# AMC_SFP.net
KiCad netlist of a schematic drawn in Altium Designer
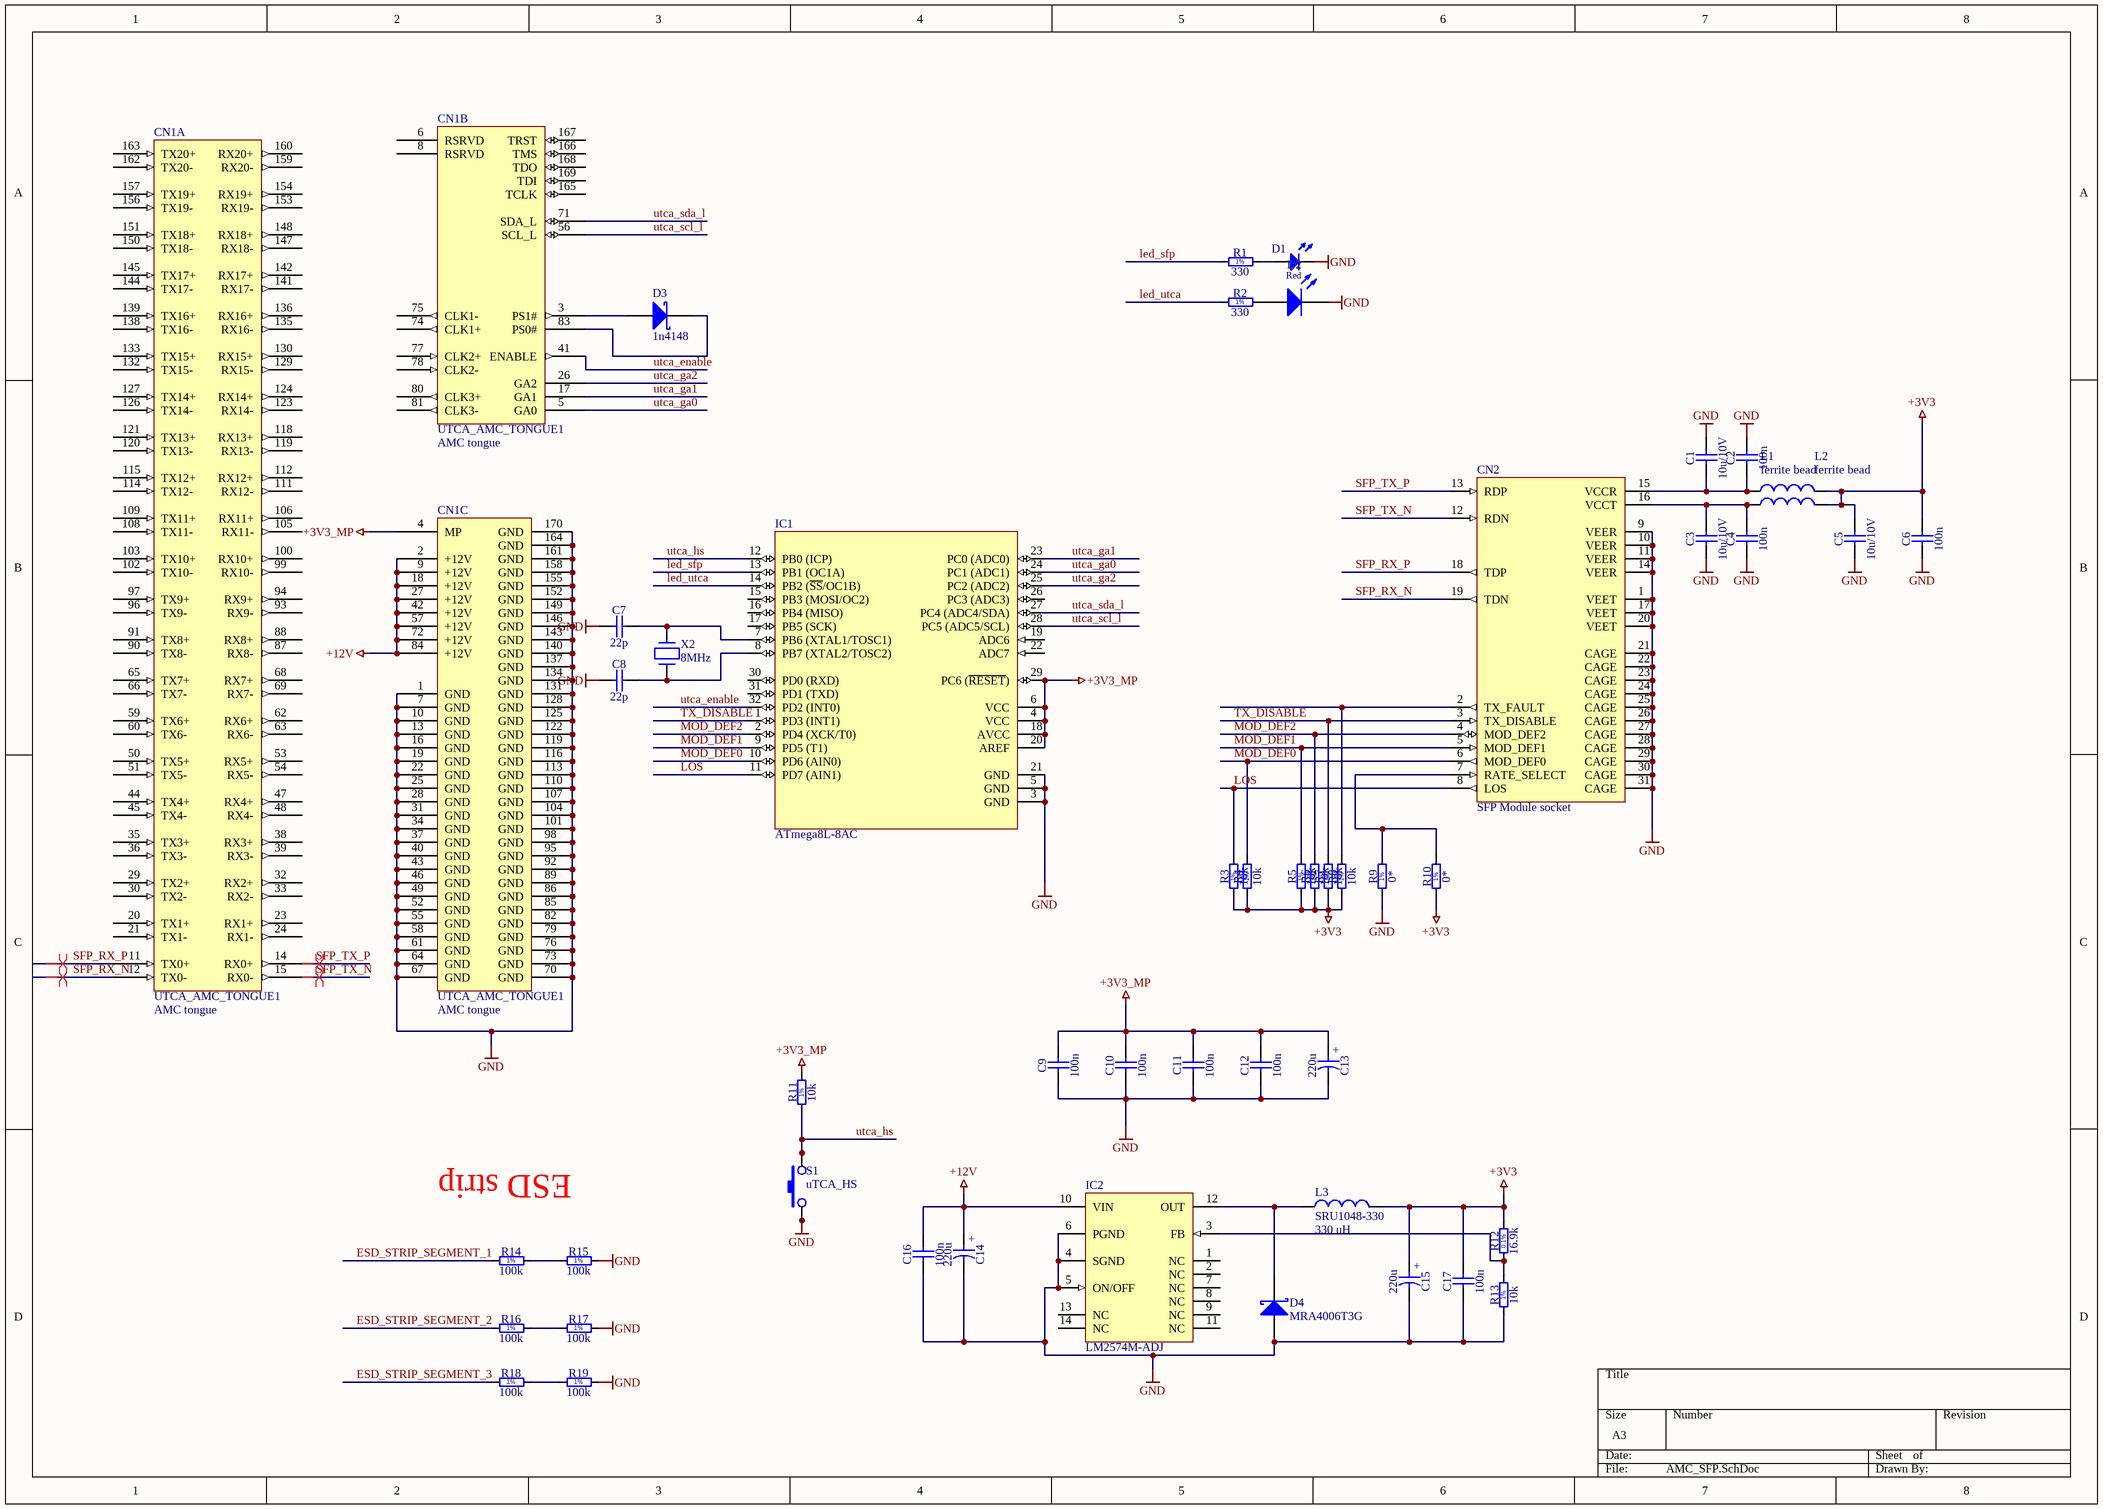
[diagram p0: AMC_SFP.SchDoc]

(export (version "E")
  (design (tool "Eeschema 10.0.6"))
  (components
    (comp (ref "C1")
      (value "10u/10V")
      (footprint "CAPC3216X140N")
      (description "Non-polarised capacitor")
      (fields
        (field (name "PART NUMBER") "CC1206_10UF_10V_10%_X7R")
        (field (name "VOLTAGE") "10V")
        (field (name "AUTHOR") "CERN DEM JLC")
      )
      (libsource (lib "Capacitors") (part "Capacitor - non polarized"))
    )
    (comp (ref "C2")
      (value "100n")
      (footprint "CAPC1608X87N")
      (description "Non-polarised capacitor")
      (fields
        (field (name "PART NUMBER") "CC0603_100NF_50V_10%_X7R")
        (field (name "VOLTAGE") "50V")
        (field (name "AUTHOR") "CERN DEM JLC")
      )
      (libsource (lib "Capacitors") (part "Capacitor - non polarized"))
    )
    (comp (ref "C3")
      (value "10u/10V")
      (footprint "CAPC3216X140N")
      (description "Non-polarised capacitor")
      (fields
        (field (name "PART NUMBER") "CC1206_10UF_10V_10%_X7R")
        (field (name "VOLTAGE") "10V")
        (field (name "AUTHOR") "CERN DEM JLC")
      )
      (libsource (lib "Capacitors") (part "Capacitor - non polarized"))
    )
    (comp (ref "C4")
      (value "100n")
      (footprint "CAPC1608X87N")
      (description "Non-polarised capacitor")
      (fields
        (field (name "PART NUMBER") "CC0603_100NF_50V_10%_X7R")
        (field (name "VOLTAGE") "50V")
        (field (name "AUTHOR") "CERN DEM JLC")
      )
      (libsource (lib "Capacitors") (part "Capacitor - non polarized"))
    )
    (comp (ref "C5")
      (value "10u/10V")
      (footprint "CAPC3216X140N")
      (description "Non-polarised capacitor")
      (fields
        (field (name "PART NUMBER") "CC1206_10UF_10V_10%_X7R")
        (field (name "VOLTAGE") "10V")
        (field (name "AUTHOR") "CERN DEM JLC")
      )
      (libsource (lib "Capacitors") (part "Capacitor - non polarized"))
    )
    (comp (ref "C6")
      (value "100n")
      (footprint "CAPC1608X87N")
      (description "Non-polarised capacitor")
      (fields
        (field (name "PART NUMBER") "CC0603_100NF_50V_10%_X7R")
        (field (name "VOLTAGE") "50V")
        (field (name "AUTHOR") "CERN DEM JLC")
      )
      (libsource (lib "Capacitors") (part "Capacitor - non polarized"))
    )
    (comp (ref "C7")
      (value "22p")
      (footprint "CAPC2012X135N")
      (description "Non-polarised capacitor")
      (fields
        (field (name "PART NUMBER") "CC0805_22PF_50V_5%_NP0")
        (field (name "VOLTAGE") "50V")
        (field (name "AUTHOR") "CERN DEM JLC")
      )
      (libsource (lib "Capacitors") (part "Capacitor - non polarized"))
    )
    (comp (ref "C8")
      (value "22p")
      (footprint "CAPC2012X135N")
      (description "Non-polarised capacitor")
      (fields
        (field (name "PART NUMBER") "CC0805_22PF_50V_5%_NP0")
        (field (name "VOLTAGE") "50V")
        (field (name "AUTHOR") "CERN DEM JLC")
      )
      (libsource (lib "Capacitors") (part "Capacitor - non polarized"))
    )
    (comp (ref "C9")
      (value "100n")
      (footprint "CAPC2012X135N")
      (description "Non-polarised capacitor")
      (fields
        (field (name "PART NUMBER") "CC0805_100NF_50V_10%_X7R")
        (field (name "VOLTAGE") "50V")
        (field (name "AUTHOR") "CERN DEM JLC")
      )
      (libsource (lib "Capacitors") (part "Capacitor - non polarized"))
    )
    (comp (ref "C10")
      (value "100n")
      (footprint "CAPC2012X135N")
      (description "Non-polarised capacitor")
      (fields
        (field (name "PART NUMBER") "CC0805_100NF_50V_10%_X7R")
        (field (name "VOLTAGE") "50V")
        (field (name "AUTHOR") "CERN DEM JLC")
      )
      (libsource (lib "Capacitors") (part "Capacitor - non polarized"))
    )
    (comp (ref "C11")
      (value "100n")
      (footprint "CAPC2012X135N")
      (description "Non-polarised capacitor")
      (fields
        (field (name "PART NUMBER") "CC0805_100NF_50V_10%_X7R")
        (field (name "VOLTAGE") "50V")
        (field (name "AUTHOR") "CERN DEM JLC")
      )
      (libsource (lib "Capacitors") (part "Capacitor - non polarized"))
    )
    (comp (ref "C12")
      (value "100n")
      (footprint "CAPC2012X135N")
      (description "Non-polarised capacitor")
      (fields
        (field (name "PART NUMBER") "CC0805_100NF_50V_10%_X7R")
        (field (name "VOLTAGE") "50V")
        (field (name "AUTHOR") "CERN DEM JLC")
      )
      (libsource (lib "Capacitors") (part "Capacitor - non polarized"))
    )
    (comp (ref "C13")
      (value "220u")
      (footprint "CAPPR350-850X600")
      (description "Polarised capacitor")
      (fields
        (field (name "PART NUMBER") "CAER_100UF_10V_20%_350-850X600_LESR0R032")
        (field (name "VOLTAGE") "10V")
        (field (name "AUTHOR") "CERN DEM JLC")
      )
      (libsource (lib "Capacitors") (part "Capacitor - polarized"))
    )
    (comp (ref "C14")
      (value "220u")
      (footprint "CAPPR350-850X600")
      (description "Polarised capacitor")
      (fields
        (field (name "PART NUMBER") "CAER_100UF_10V_20%_350-850X600_LESR0R032")
        (field (name "VOLTAGE") "10V")
        (field (name "AUTHOR") "CERN DEM JLC")
      )
      (libsource (lib "Capacitors") (part "Capacitor - polarized"))
    )
    (comp (ref "C15")
      (value "220u")
      (footprint "CAPPR350-850X600")
      (description "Polarised capacitor")
      (fields
        (field (name "PART NUMBER") "CAER_100UF_10V_20%_350-850X600_LESR0R032")
        (field (name "VOLTAGE") "10V")
        (field (name "AUTHOR") "CERN DEM JLC")
      )
      (libsource (lib "Capacitors") (part "Capacitor - polarized"))
    )
    (comp (ref "C16")
      (value "100n")
      (footprint "CAPC1608X87N")
      (description "Non-polarised capacitor")
      (fields
        (field (name "PART NUMBER") "CC0603_100NF_50V_10%_X7R")
        (field (name "VOLTAGE") "50V")
        (field (name "AUTHOR") "CERN DEM JLC")
      )
      (libsource (lib "Capacitors") (part "Capacitor - non polarized"))
    )
    (comp (ref "C17")
      (value "100n")
      (footprint "CAPC1608X87N")
      (description "Non-polarised capacitor")
      (fields
        (field (name "PART NUMBER") "CC0603_100NF_50V_10%_X7R")
        (field (name "VOLTAGE") "50V")
        (field (name "AUTHOR") "CERN DEM JLC")
      )
      (libsource (lib "Capacitors") (part "Capacitor - non polarized"))
    )
    (comp (ref "CN1")
      (value "UTCA_AMC_TONGUE1")
      (footprint "UTCA_AMC_TONGUE")
      (description "AMC1.0 connector")
      (fields (field (name "ALTIUM_VALUE") "AMC tongue"))
      (libsource (lib "wr_switch") (part "UTCA_AMC_TONGUE1"))
    )
    (comp (ref "CN2")
      (value "SFP Module socket")
      (footprint "SFP_SINGLE_PORT")
      (description "Socket for SFP module")
      (libsource (lib "wr_switch") (part "SFP_SOCKET_SINGLE"))
    )
    (comp (ref "D1")
      (value "Green")
      (footprint "LED_3MM_RED_1C-2A")
      (description "LED Red 1C 2A")
      (fields
        (field (name "PART NUMBER") "LED_AVAGO_HLMP-1700")
        (field (name "MANUFACTURER") "AVAGO TECHNOLOGIES")
        (field (name "AUTHOR") "CERN DEM JLC")
      )
      (libsource (lib "ICs And Semiconductors") (part "LED Red 1C 2A"))
    )
    (comp (ref "D2")
      (value "LED")
      (footprint "CD1608-0603")
      (description "Chip LED (any color)")
      (fields (field (name "PUBLISHER") "Altium Limited"))
      (libsource (lib "wr_switch") (part "LED0"))
    )
    (comp (ref "D3")
      (value "1n4148")
      (footprint "CD2012-0805")
      (description "Schottky Diode")
      (fields (field (name "PUBLISHER") "Altium Limited"))
      (libsource (lib "wr_switch") (part "D Schottky"))
    )
    (comp (ref "D4")
      (value "MRA4006T3G")
      (footprint "SMB")
      (description "Schottky Diode")
      (fields (field (name "PUBLISHER") "Altium Limited"))
      (libsource (lib "wr_switch") (part "D Schottky"))
    )
    (comp (ref "IC1")
      (value "ATmega8L-8AC")
      (footprint "32A_N")
      (description "8-Bit AVR Microcontroller with 8K Bytes of In-System Programmable Flash Memory")
      (fields (field (name "PUBLISHER") "Altium Limited"))
      (libsource (lib "Atmel Microcontroller 8-Bit AVR") (part "ATmega8L-8AC"))
    )
    (comp (ref "IC2")
      (value "LM2574M-ADJ")
      (footprint "M14B_N")
      (description "SIMPLE SWITCHER 0.5A Step-Down Voltage Regulator")
      (fields
        (field (name "MANUFACTURER") "National Semiconductor")
        (field (name "DIGIKEYPARTNUMBER") "LM2574M-ADJ-ND")
        (field (name "PUBLISHER") "Altium Limited")
      )
      (libsource (lib "NSC Switcher") (part "LM2574M-ADJ"))
    )
    (comp (ref "L1")
      (value "ferrite bead")
      (footprint "INDC2012-0805")
      (description "Ferrite bead")
      (fields (field (name "Comment") "Inductor") (field (name "PUBLISHER") "Altium Limited"))
      (libsource (lib "Miscellaneous Devices") (part "Inductor"))
    )
    (comp (ref "L2")
      (value "ferrite bead")
      (footprint "INDC2012-0805")
      (description "Ferrite bead")
      (fields (field (name "Comment") "Inductor") (field (name "PUBLISHER") "Altium Limited"))
      (libsource (lib "Miscellaneous Devices") (part "Inductor"))
    )
    (comp (ref "L3")
      (value "SRU1048-330")
      (footprint "L_BOURNS_SRU1048")
      (description "Inductor")
      (fields (field (name "ALTIUM_VALUE") "330 uH") (field (name "PUBLISHER") "Altium Limited"))
      (libsource (lib "wr_switch") (part "Inductor"))
    )
    (comp (ref "R1")
      (value "330")
      (footprint "RESC2012X60N")
      (description "Resistor - 1%")
      (fields
        (field (name "PART NUMBER") "R0805_330R_1%_0.125W_100PPM")
        (field (name "POWER") "0.125W")
        (field (name "AUTHOR") "CERN DEM JLC")
      )
      (libsource (lib "Resistors") (part "Resistor - 1%"))
    )
    (comp (ref "R2")
      (value "330")
      (footprint "RESC2012X60N")
      (description "Resistor - 1%")
      (fields
        (field (name "PART NUMBER") "R0805_330R_1%_0.125W_100PPM")
        (field (name "POWER") "0.125W")
        (field (name "AUTHOR") "CERN DEM JLC")
      )
      (libsource (lib "Resistors") (part "Resistor - 1%"))
    )
    (comp (ref "R3")
      (value "10k")
      (footprint "RESC1608X55N")
      (description "Resistor - 1%")
      (fields
        (field (name "PART NUMBER") "R0603_10K_1%_0.1W_100PPM")
        (field (name "POWER") "0.1W")
        (field (name "AUTHOR") "CERN DEM JLC")
      )
      (libsource (lib "Resistors") (part "Resistor - 1%"))
    )
    (comp (ref "R4")
      (value "10k")
      (footprint "RESC1608X55N")
      (description "Resistor - 1%")
      (fields
        (field (name "PART NUMBER") "R0603_10K_1%_0.1W_100PPM")
        (field (name "POWER") "0.1W")
        (field (name "AUTHOR") "CERN DEM JLC")
      )
      (libsource (lib "Resistors") (part "Resistor - 1%"))
    )
    (comp (ref "R5")
      (value "10k")
      (footprint "RESC1608X55N")
      (description "Resistor - 1%")
      (fields
        (field (name "PART NUMBER") "R0603_10K_1%_0.1W_100PPM")
        (field (name "POWER") "0.1W")
        (field (name "AUTHOR") "CERN DEM JLC")
      )
      (libsource (lib "Resistors") (part "Resistor - 1%"))
    )
    (comp (ref "R6")
      (value "10k")
      (footprint "RESC1608X55N")
      (description "Resistor - 1%")
      (fields
        (field (name "PART NUMBER") "R0603_10K_1%_0.1W_100PPM")
        (field (name "POWER") "0.1W")
        (field (name "AUTHOR") "CERN DEM JLC")
      )
      (libsource (lib "Resistors") (part "Resistor - 1%"))
    )
    (comp (ref "R7")
      (value "10k")
      (footprint "RESC1608X55N")
      (description "Resistor - 1%")
      (fields
        (field (name "PART NUMBER") "R0603_10K_1%_0.1W_100PPM")
        (field (name "POWER") "0.1W")
        (field (name "AUTHOR") "CERN DEM JLC")
      )
      (libsource (lib "Resistors") (part "Resistor - 1%"))
    )
    (comp (ref "R8")
      (value "10k")
      (footprint "RESC1608X55N")
      (description "Resistor - 1%")
      (fields
        (field (name "PART NUMBER") "R0603_10K_1%_0.1W_100PPM")
        (field (name "POWER") "0.1W")
        (field (name "AUTHOR") "CERN DEM JLC")
      )
      (libsource (lib "Resistors") (part "Resistor - 1%"))
    )
    (comp (ref "R9")
      (value "0*")
      (footprint "RESC1608X55N")
      (description "Resistor - 1%")
      (fields
        (field (name "PART NUMBER") "R0603_0R_JUMPER")
        (field (name "MANUFACTURER") "GENERIC")
        (field (name "AUTHOR") "CERN DEM JLC")
      )
      (libsource (lib "Resistors") (part "Resistor - 1%"))
    )
    (comp (ref "R10")
      (value "0*")
      (footprint "RESC1608X55N")
      (description "Resistor - 1%")
      (fields
        (field (name "PART NUMBER") "R0603_0R_JUMPER")
        (field (name "MANUFACTURER") "GENERIC")
        (field (name "AUTHOR") "CERN DEM JLC")
      )
      (libsource (lib "Resistors") (part "Resistor - 1%"))
    )
    (comp (ref "R11")
      (value "10k")
      (footprint "RESC1608X55N")
      (description "Resistor - 1%")
      (fields
        (field (name "PART NUMBER") "R0603_10K_1%_0.1W_100PPM")
        (field (name "POWER") "0.1W")
        (field (name "AUTHOR") "CERN DEM JLC")
      )
      (libsource (lib "Resistors") (part "Resistor - 1%"))
    )
    (comp (ref "R12")
      (value "16.9k")
      (footprint "RESC2012X60N")
      (description "Resistor - 0.1%")
      (fields
        (field (name "PART NUMBER") "R0805_16K9_0.1%_0.1W_10PPM")
        (field (name "POWER") "0.1W")
        (field (name "AUTHOR") "CERN DEM JLC")
      )
      (libsource (lib "Resistors") (part "Resistor - 0.1%"))
    )
    (comp (ref "R13")
      (value "10k")
      (footprint "RESC2012X60N")
      (description "Resistor - 1%")
      (fields
        (field (name "PART NUMBER") "R0805_10K_1%_0.125W_100PPM")
        (field (name "POWER") "0.125W")
        (field (name "AUTHOR") "CERN DEM JLC")
      )
      (libsource (lib "Resistors") (part "Resistor - 1%"))
    )
    (comp (ref "R14")
      (value "100k")
      (footprint "RESC3216X65N")
      (description "Resistor - 1%")
      (fields
        (field (name "PART NUMBER") "R1206_100K_1%_0.25W_100PPM")
        (field (name "POWER") "0.25W")
        (field (name "AUTHOR") "CERN DEM JLC")
      )
      (libsource (lib "Resistors") (part "Resistor - 1%"))
    )
    (comp (ref "R15")
      (value "100k")
      (footprint "RESC3216X65N")
      (description "Resistor - 1%")
      (fields
        (field (name "PART NUMBER") "R1206_100K_1%_0.25W_100PPM")
        (field (name "POWER") "0.25W")
        (field (name "AUTHOR") "CERN DEM JLC")
      )
      (libsource (lib "Resistors") (part "Resistor - 1%"))
    )
    (comp (ref "R16")
      (value "100k")
      (footprint "RESC3216X65N")
      (description "Resistor - 1%")
      (fields
        (field (name "PART NUMBER") "R1206_100K_1%_0.25W_100PPM")
        (field (name "POWER") "0.25W")
        (field (name "AUTHOR") "CERN DEM JLC")
      )
      (libsource (lib "Resistors") (part "Resistor - 1%"))
    )
    (comp (ref "R17")
      (value "100k")
      (footprint "RESC3216X65N")
      (description "Resistor - 1%")
      (fields
        (field (name "PART NUMBER") "R1206_100K_1%_0.25W_100PPM")
        (field (name "POWER") "0.25W")
        (field (name "AUTHOR") "CERN DEM JLC")
      )
      (libsource (lib "Resistors") (part "Resistor - 1%"))
    )
    (comp (ref "R18")
      (value "100k")
      (footprint "RESC3216X65N")
      (description "Resistor - 1%")
      (fields
        (field (name "PART NUMBER") "R1206_100K_1%_0.25W_100PPM")
        (field (name "POWER") "0.25W")
        (field (name "AUTHOR") "CERN DEM JLC")
      )
      (libsource (lib "Resistors") (part "Resistor - 1%"))
    )
    (comp (ref "R19")
      (value "100k")
      (footprint "RESC3216X65N")
      (description "Resistor - 1%")
      (fields
        (field (name "PART NUMBER") "R1206_100K_1%_0.25W_100PPM")
        (field (name "POWER") "0.25W")
        (field (name "AUTHOR") "CERN DEM JLC")
      )
      (libsource (lib "Resistors") (part "Resistor - 1%"))
    )
    (comp (ref "S1")
      (value "uTCA_HS")
      (footprint "uTCA_HOTSWAP_SWITCH")
      (description "Push button")
      (libsource (lib "wr_switch") (part "uTCA_HOTSWAP_SWITCH"))
    )
    (comp (ref "X2")
      (value "8MHz")
      (footprint "HC-49US")
      (description "Crystal oscillator")
      (libsource (lib "LIBRARY_SCH") (part "X_CRYSTAL"))
    )
  )
  (nets
    (net (code "1") (name "+3V3") (class "Default")
      (node (ref "C15") (pin "1") (pinfunction "1_1") (pintype "passive"))
      (node (ref "C17") (pin "2") (pinfunction "2_2") (pintype "passive"))
      (node (ref "C5") (pin "2") (pinfunction "2_2") (pintype "passive"))
      (node (ref "C6") (pin "2") (pinfunction "2_2") (pintype "passive"))
      (node (ref "L1") (pin "2") (pinfunction "2_2") (pintype "passive"))
      (node (ref "L2") (pin "2") (pinfunction "2_2") (pintype "passive"))
      (node (ref "L3") (pin "2") (pinfunction "2_2") (pintype "passive"))
      (node (ref "R10") (pin "1") (pinfunction "1_1") (pintype "passive"))
      (node (ref "R12") (pin "2") (pinfunction "2_2") (pintype "passive"))
      (node (ref "R3") (pin "1") (pinfunction "1_1") (pintype "passive"))
      (node (ref "R4") (pin "1") (pinfunction "1_1") (pintype "passive"))
      (node (ref "R5") (pin "1") (pinfunction "1_1") (pintype "passive"))
      (node (ref "R6") (pin "1") (pinfunction "1_1") (pintype "passive"))
      (node (ref "R7") (pin "1") (pinfunction "1_1") (pintype "passive"))
      (node (ref "R8") (pin "1") (pinfunction "1_1") (pintype "passive"))
    )
    (net (code "2") (name "+3V3_MP") (class "Default")
      (node (ref "C10") (pin "2") (pinfunction "2_2") (pintype "passive"))
      (node (ref "C11") (pin "2") (pinfunction "2_2") (pintype "passive"))
      (node (ref "C12") (pin "2") (pinfunction "2_2") (pintype "passive"))
      (node (ref "C13") (pin "1") (pinfunction "1_1") (pintype "passive"))
      (node (ref "C9") (pin "2") (pinfunction "2_2") (pintype "passive"))
      (node (ref "CN1") (pin "4") (pinfunction "MP_4") (pintype "power_in"))
      (node (ref "IC1") (pin "18") (pinfunction "AVCC_18") (pintype "power_in"))
      (node (ref "IC1") (pin "20") (pinfunction "AREF_20") (pintype "passive"))
      (node (ref "IC1") (pin "29") (pinfunction "PC6_(~{RESET})_29") (pintype "bidirectional"))
      (node (ref "IC1") (pin "4") (pinfunction "VCC_4") (pintype "power_in"))
      (node (ref "IC1") (pin "6") (pinfunction "VCC_6") (pintype "power_in"))
      (node (ref "R11") (pin "2") (pinfunction "2_2") (pintype "passive"))
    )
    (net (code "3") (name "+12V") (class "Default")
      (node (ref "C14") (pin "1") (pinfunction "1_1") (pintype "passive"))
      (node (ref "C16") (pin "2") (pinfunction "2_2") (pintype "passive"))
      (node (ref "CN1") (pin "18") (pinfunction "+12V_18") (pintype "power_in"))
      (node (ref "CN1") (pin "2") (pinfunction "+12V_2") (pintype "power_in"))
      (node (ref "CN1") (pin "27") (pinfunction "+12V_27") (pintype "power_in"))
      (node (ref "CN1") (pin "42") (pinfunction "+12V_42") (pintype "power_in"))
      (node (ref "CN1") (pin "57") (pinfunction "+12V_57") (pintype "power_in"))
      (node (ref "CN1") (pin "72") (pinfunction "+12V_72") (pintype "power_in"))
      (node (ref "CN1") (pin "84") (pinfunction "+12V_84") (pintype "power_in"))
      (node (ref "CN1") (pin "9") (pinfunction "+12V_9") (pintype "power_in"))
      (node (ref "IC2") (pin "10") (pinfunction "VIN_10") (pintype "power_in"))
    )
    (net (code "4") (name "/ESD_STRIP_SEGMENT_1") (class "Default")
      (node (ref "R14") (pin "1") (pinfunction "1_1") (pintype "passive"))
    )
    (net (code "5") (name "/ESD_STRIP_SEGMENT_2") (class "Default")
      (node (ref "R16") (pin "1") (pinfunction "1_1") (pintype "passive"))
    )
    (net (code "6") (name "/ESD_STRIP_SEGMENT_3") (class "Default")
      (node (ref "R18") (pin "1") (pinfunction "1_1") (pintype "passive"))
    )
    (net (code "7") (name "/LOS") (class "Default")
      (node (ref "CN2") (pin "8") (pinfunction "LOS_8") (pintype "output"))
      (node (ref "IC1") (pin "11") (pinfunction "PD7_(AIN1)_11") (pintype "bidirectional"))
      (node (ref "R3") (pin "2") (pinfunction "2_2") (pintype "passive"))
    )
    (net (code "8") (name "/MOD_DEF0") (class "Default")
      (node (ref "CN2") (pin "6") (pinfunction "MOD_DEF0_6") (pintype "output"))
      (node (ref "IC1") (pin "10") (pinfunction "PD6_(AIN0)_10") (pintype "bidirectional"))
      (node (ref "R4") (pin "2") (pinfunction "2_2") (pintype "passive"))
    )
    (net (code "9") (name "/MOD_DEF1") (class "Default")
      (node (ref "CN2") (pin "5") (pinfunction "MOD_DEF1_5") (pintype "input"))
      (node (ref "IC1") (pin "9") (pinfunction "PD5_(T1)_9") (pintype "bidirectional"))
      (node (ref "R5") (pin "2") (pinfunction "2_2") (pintype "passive"))
    )
    (net (code "10") (name "/MOD_DEF2") (class "Default")
      (node (ref "CN2") (pin "4") (pinfunction "MOD_DEF2_4") (pintype "bidirectional"))
      (node (ref "IC1") (pin "2") (pinfunction "PD4_(XCK/T0)_2") (pintype "bidirectional"))
      (node (ref "R6") (pin "2") (pinfunction "2_2") (pintype "passive"))
    )
    (net (code "11") (name "/SFP_RX_N") (class "Default")
      (node (ref "CN1") (pin "12") (pinfunction "TX0-_12") (pintype "input"))
      (node (ref "CN2") (pin "19") (pinfunction "TDN_19") (pintype "output"))
    )
    (net (code "12") (name "/SFP_RX_P") (class "Default")
      (node (ref "CN1") (pin "11") (pinfunction "TX0+_11") (pintype "input"))
      (node (ref "CN2") (pin "18") (pinfunction "TDP_18") (pintype "output"))
    )
    (net (code "13") (name "/SFP_TX_N") (class "Default")
      (node (ref "CN1") (pin "15") (pinfunction "RX0-_15") (pintype "output"))
      (node (ref "CN2") (pin "12") (pinfunction "RDN_12") (pintype "input"))
    )
    (net (code "14") (name "/SFP_TX_P") (class "Default")
      (node (ref "CN1") (pin "14") (pinfunction "RX0+_14") (pintype "output"))
      (node (ref "CN2") (pin "13") (pinfunction "RDP_13") (pintype "input"))
    )
    (net (code "15") (name "/TX_DISABLE") (class "Default")
      (node (ref "CN2") (pin "3") (pinfunction "TX_DISABLE_3") (pintype "input"))
      (node (ref "IC1") (pin "1") (pinfunction "PD3_(INT1)_1") (pintype "bidirectional"))
      (node (ref "R7") (pin "2") (pinfunction "2_2") (pintype "passive"))
    )
    (net (code "16") (name "/led_sfp") (class "Default")
      (node (ref "IC1") (pin "13") (pinfunction "PB1_(OC1A)_13") (pintype "bidirectional"))
      (node (ref "R1") (pin "1") (pinfunction "1_1") (pintype "passive"))
    )
    (net (code "17") (name "/led_utca") (class "Default")
      (node (ref "IC1") (pin "14") (pinfunction "PB2_(~{SS}/OC1B)_14") (pintype "bidirectional"))
      (node (ref "R2") (pin "1") (pinfunction "1_1") (pintype "passive"))
    )
    (net (code "18") (name "/utca_enable") (class "Default")
      (node (ref "CN1") (pin "41") (pinfunction "ENABLE_41") (pintype "output"))
      (node (ref "IC1") (pin "32") (pinfunction "PD2_(INT0)_32") (pintype "bidirectional"))
    )
    (net (code "19") (name "/utca_ga0") (class "Default")
      (node (ref "CN1") (pin "5") (pinfunction "GA0_5") (pintype "passive"))
      (node (ref "IC1") (pin "24") (pinfunction "PC1_(ADC1)_24") (pintype "bidirectional"))
    )
    (net (code "20") (name "/utca_ga1") (class "Default")
      (node (ref "CN1") (pin "17") (pinfunction "GA1_17") (pintype "passive"))
      (node (ref "IC1") (pin "23") (pinfunction "PC0_(ADC0)_23") (pintype "bidirectional"))
    )
    (net (code "21") (name "/utca_ga2") (class "Default")
      (node (ref "CN1") (pin "26") (pinfunction "GA2_26") (pintype "passive"))
      (node (ref "IC1") (pin "25") (pinfunction "PC2_(ADC2)_25") (pintype "bidirectional"))
    )
    (net (code "22") (name "/utca_hs") (class "Default")
      (node (ref "IC1") (pin "12") (pinfunction "PB0_(ICP)_12") (pintype "bidirectional"))
      (node (ref "R11") (pin "1") (pinfunction "1_1") (pintype "passive"))
      (node (ref "S1") (pin "B") (pinfunction "B_B") (pintype "passive"))
      (node (ref "S1") (pin "D") (pinfunction "D_D") (pintype "passive"))
    )
    (net (code "23") (name "/utca_scl_l") (class "Default")
      (node (ref "CN1") (pin "56") (pinfunction "SCL_L_56") (pintype "bidirectional"))
      (node (ref "IC1") (pin "28") (pinfunction "PC5_(ADC5/SCL)_28") (pintype "bidirectional"))
    )
    (net (code "24") (name "/utca_sda_l") (class "Default")
      (node (ref "CN1") (pin "71") (pinfunction "SDA_L_71") (pintype "bidirectional"))
      (node (ref "IC1") (pin "27") (pinfunction "PC4_(ADC4/SDA)_27") (pintype "bidirectional"))
    )
    (net (code "25") (name "GND") (class "Default")
      (node (ref "C1") (pin "2") (pinfunction "2_2") (pintype "passive"))
      (node (ref "C10") (pin "1") (pinfunction "1_1") (pintype "passive"))
      (node (ref "C11") (pin "1") (pinfunction "1_1") (pintype "passive"))
      (node (ref "C12") (pin "1") (pinfunction "1_1") (pintype "passive"))
      (node (ref "C13") (pin "2") (pinfunction "2_2") (pintype "passive"))
      (node (ref "C14") (pin "2") (pinfunction "2_2") (pintype "passive"))
      (node (ref "C15") (pin "2") (pinfunction "2_2") (pintype "passive"))
      (node (ref "C16") (pin "1") (pinfunction "1_1") (pintype "passive"))
      (node (ref "C17") (pin "1") (pinfunction "1_1") (pintype "passive"))
      (node (ref "C2") (pin "2") (pinfunction "2_2") (pintype "passive"))
      (node (ref "C3") (pin "1") (pinfunction "1_1") (pintype "passive"))
      (node (ref "C4") (pin "1") (pinfunction "1_1") (pintype "passive"))
      (node (ref "C5") (pin "1") (pinfunction "1_1") (pintype "passive"))
      (node (ref "C6") (pin "1") (pinfunction "1_1") (pintype "passive"))
      (node (ref "C7") (pin "1") (pinfunction "1_1") (pintype "passive"))
      (node (ref "C8") (pin "1") (pinfunction "1_1") (pintype "passive"))
      (node (ref "C9") (pin "1") (pinfunction "1_1") (pintype "passive"))
      (node (ref "CN1") (pin "1") (pinfunction "GND_1") (pintype "power_in"))
      (node (ref "CN1") (pin "10") (pinfunction "GND_10") (pintype "power_in"))
      (node (ref "CN1") (pin "101") (pinfunction "GND_101") (pintype "power_in"))
      (node (ref "CN1") (pin "104") (pinfunction "GND_104") (pintype "power_in"))
      (node (ref "CN1") (pin "107") (pinfunction "GND_107") (pintype "power_in"))
      (node (ref "CN1") (pin "110") (pinfunction "GND_110") (pintype "power_in"))
      (node (ref "CN1") (pin "113") (pinfunction "GND_113") (pintype "power_in"))
      (node (ref "CN1") (pin "116") (pinfunction "GND_116") (pintype "power_in"))
      (node (ref "CN1") (pin "119") (pinfunction "GND_119") (pintype "power_in"))
      (node (ref "CN1") (pin "122") (pinfunction "GND_122") (pintype "power_in"))
      (node (ref "CN1") (pin "125") (pinfunction "GND_125") (pintype "power_in"))
      (node (ref "CN1") (pin "128") (pinfunction "GND_128") (pintype "power_in"))
      (node (ref "CN1") (pin "13") (pinfunction "GND_13") (pintype "power_in"))
      (node (ref "CN1") (pin "131") (pinfunction "GND_131") (pintype "power_in"))
      (node (ref "CN1") (pin "134") (pinfunction "GND_134") (pintype "power_in"))
      (node (ref "CN1") (pin "137") (pinfunction "GND_137") (pintype "power_in"))
      (node (ref "CN1") (pin "140") (pinfunction "GND_140") (pintype "power_in"))
      (node (ref "CN1") (pin "143") (pinfunction "GND_143") (pintype "power_in"))
      (node (ref "CN1") (pin "146") (pinfunction "GND_146") (pintype "power_in"))
      (node (ref "CN1") (pin "149") (pinfunction "GND_149") (pintype "power_in"))
      (node (ref "CN1") (pin "152") (pinfunction "GND_152") (pintype "power_in"))
      (node (ref "CN1") (pin "155") (pinfunction "GND_155") (pintype "power_in"))
      (node (ref "CN1") (pin "158") (pinfunction "GND_158") (pintype "power_in"))
      (node (ref "CN1") (pin "16") (pinfunction "GND_16") (pintype "power_in"))
      (node (ref "CN1") (pin "161") (pinfunction "GND_161") (pintype "power_in"))
      (node (ref "CN1") (pin "164") (pinfunction "GND_164") (pintype "power_in"))
      (node (ref "CN1") (pin "170") (pinfunction "GND_170") (pintype "power_in"))
      (node (ref "CN1") (pin "19") (pinfunction "GND_19") (pintype "power_in"))
      (node (ref "CN1") (pin "22") (pinfunction "GND_22") (pintype "power_in"))
      (node (ref "CN1") (pin "25") (pinfunction "GND_25") (pintype "power_in"))
      (node (ref "CN1") (pin "28") (pinfunction "GND_28") (pintype "power_in"))
      (node (ref "CN1") (pin "31") (pinfunction "GND_31") (pintype "power_in"))
      (node (ref "CN1") (pin "34") (pinfunction "GND_34") (pintype "power_in"))
      (node (ref "CN1") (pin "37") (pinfunction "GND_37") (pintype "power_in"))
      (node (ref "CN1") (pin "40") (pinfunction "GND_40") (pintype "power_in"))
      (node (ref "CN1") (pin "43") (pinfunction "GND_43") (pintype "power_in"))
      (node (ref "CN1") (pin "46") (pinfunction "GND_46") (pintype "power_in"))
      (node (ref "CN1") (pin "49") (pinfunction "GND_49") (pintype "power_in"))
      (node (ref "CN1") (pin "52") (pinfunction "GND_52") (pintype "power_in"))
      (node (ref "CN1") (pin "55") (pinfunction "GND_55") (pintype "power_in"))
      (node (ref "CN1") (pin "58") (pinfunction "GND_58") (pintype "power_in"))
      (node (ref "CN1") (pin "61") (pinfunction "GND_61") (pintype "power_in"))
      (node (ref "CN1") (pin "64") (pinfunction "GND_64") (pintype "power_in"))
      (node (ref "CN1") (pin "67") (pinfunction "GND_67") (pintype "power_in"))
      (node (ref "CN1") (pin "7") (pinfunction "GND_7") (pintype "power_in"))
      (node (ref "CN1") (pin "70") (pinfunction "GND_70") (pintype "power_in"))
      (node (ref "CN1") (pin "73") (pinfunction "GND_73") (pintype "power_in"))
      (node (ref "CN1") (pin "76") (pinfunction "GND_76") (pintype "power_in"))
      (node (ref "CN1") (pin "79") (pinfunction "GND_79") (pintype "power_in"))
      (node (ref "CN1") (pin "82") (pinfunction "GND_82") (pintype "power_in"))
      (node (ref "CN1") (pin "85") (pinfunction "GND_85") (pintype "power_in"))
      (node (ref "CN1") (pin "86") (pinfunction "GND_86") (pintype "power_in"))
      (node (ref "CN1") (pin "89") (pinfunction "GND_89") (pintype "power_in"))
      (node (ref "CN1") (pin "92") (pinfunction "GND_92") (pintype "power_in"))
      (node (ref "CN1") (pin "95") (pinfunction "GND_95") (pintype "power_in"))
      (node (ref "CN1") (pin "98") (pinfunction "GND_98") (pintype "power_in"))
      (node (ref "CN2") (pin "1") (pinfunction "VEET_1") (pintype "power_in"))
      (node (ref "CN2") (pin "10") (pinfunction "VEER_10") (pintype "power_in"))
      (node (ref "CN2") (pin "11") (pinfunction "VEER_11") (pintype "power_in"))
      (node (ref "CN2") (pin "14") (pinfunction "VEER_14") (pintype "power_in"))
      (node (ref "CN2") (pin "17") (pinfunction "VEET_17") (pintype "power_in"))
      (node (ref "CN2") (pin "20") (pinfunction "VEET_20") (pintype "power_in"))
      (node (ref "CN2") (pin "21") (pinfunction "CAGE_21") (pintype "power_in"))
      (node (ref "CN2") (pin "22") (pinfunction "CAGE_22") (pintype "power_in"))
      (node (ref "CN2") (pin "23") (pinfunction "CAGE_23") (pintype "power_in"))
      (node (ref "CN2") (pin "24") (pinfunction "CAGE_24") (pintype "power_in"))
      (node (ref "CN2") (pin "25") (pinfunction "CAGE_25") (pintype "power_in"))
      (node (ref "CN2") (pin "26") (pinfunction "CAGE_26") (pintype "power_in"))
      (node (ref "CN2") (pin "27") (pinfunction "CAGE_27") (pintype "power_in"))
      (node (ref "CN2") (pin "28") (pinfunction "CAGE_28") (pintype "power_in"))
      (node (ref "CN2") (pin "29") (pinfunction "CAGE_29") (pintype "power_in"))
      (node (ref "CN2") (pin "30") (pinfunction "CAGE_30") (pintype "power_in"))
      (node (ref "CN2") (pin "31") (pinfunction "CAGE_31") (pintype "power_in"))
      (node (ref "CN2") (pin "9") (pinfunction "VEER_9") (pintype "power_in"))
      (node (ref "D1") (pin "1") (pinfunction "C_1") (pintype "passive"))
      (node (ref "D2") (pin "2") (pinfunction "K_2") (pintype "passive"))
      (node (ref "D4") (pin "1") (pinfunction "A_1") (pintype "passive"))
      (node (ref "IC1") (pin "21") (pinfunction "GND_21") (pintype "power_in"))
      (node (ref "IC1") (pin "3") (pinfunction "GND_3") (pintype "power_in"))
      (node (ref "IC1") (pin "5") (pinfunction "GND_5") (pintype "power_in"))
      (node (ref "IC2") (pin "4") (pinfunction "SGND_4") (pintype "power_in"))
      (node (ref "IC2") (pin "5") (pinfunction "ON/OFF_5") (pintype "input"))
      (node (ref "IC2") (pin "6") (pinfunction "PGND_6") (pintype "power_in"))
      (node (ref "R13") (pin "1") (pinfunction "1_1") (pintype "passive"))
      (node (ref "R15") (pin "2") (pinfunction "2_2") (pintype "passive"))
      (node (ref "R17") (pin "2") (pinfunction "2_2") (pintype "passive"))
      (node (ref "R19") (pin "2") (pinfunction "2_2") (pintype "passive"))
      (node (ref "R9") (pin "1") (pinfunction "1_1") (pintype "passive"))
      (node (ref "S1") (pin "A") (pinfunction "A_A") (pintype "passive"))
      (node (ref "S1") (pin "C") (pinfunction "C_C") (pintype "passive"))
    )
    (net (code "26") (name "Net-(CN1B-PS0#)") (class "Default")
      (node (ref "CN1") (pin "83") (pinfunction "PS0#_83") (pintype "passive"))
      (node (ref "D3") (pin "2") (pinfunction "K_2") (pintype "passive"))
    )
    (net (code "27") (name "Net-(CN1B-PS1#)") (class "Default")
      (node (ref "CN1") (pin "3") (pinfunction "PS1#_3") (pintype "output"))
      (node (ref "D3") (pin "1") (pinfunction "A_1") (pintype "passive"))
    )
    (net (code "28") (name "Net-(CN2-RATE_SELECT)") (class "Default")
      (node (ref "CN2") (pin "7") (pinfunction "RATE_SELECT_7") (pintype "input"))
      (node (ref "R10") (pin "2") (pinfunction "2_2") (pintype "passive"))
      (node (ref "R9") (pin "2") (pinfunction "2_2") (pintype "passive"))
    )
    (net (code "29") (name "Net-(CN2-TX_FAULT)") (class "Default")
      (node (ref "CN2") (pin "2") (pinfunction "TX_FAULT_2") (pintype "output"))
      (node (ref "R8") (pin "2") (pinfunction "2_2") (pintype "passive"))
    )
    (net (code "30") (name "Net-(CN2-VCCR)") (class "Default")
      (node (ref "C1") (pin "1") (pinfunction "1_1") (pintype "passive"))
      (node (ref "C2") (pin "1") (pinfunction "1_1") (pintype "passive"))
      (node (ref "CN2") (pin "15") (pinfunction "VCCR_15") (pintype "power_in"))
      (node (ref "L2") (pin "1") (pinfunction "1_1") (pintype "passive"))
    )
    (net (code "31") (name "Net-(CN2-VCCT)") (class "Default")
      (node (ref "C3") (pin "2") (pinfunction "2_2") (pintype "passive"))
      (node (ref "C4") (pin "2") (pinfunction "2_2") (pintype "passive"))
      (node (ref "CN2") (pin "16") (pinfunction "VCCT_16") (pintype "power_in"))
      (node (ref "L1") (pin "1") (pinfunction "1_1") (pintype "passive"))
    )
    (net (code "32") (name "Net-(D1-A)") (class "Default")
      (node (ref "D1") (pin "2") (pinfunction "A_2") (pintype "passive"))
      (node (ref "R1") (pin "2") (pinfunction "2_2") (pintype "passive"))
    )
    (net (code "33") (name "Net-(D2-A)") (class "Default")
      (node (ref "D2") (pin "1") (pinfunction "A_1") (pintype "passive"))
      (node (ref "R2") (pin "2") (pinfunction "2_2") (pintype "passive"))
    )
    (net (code "34") (name "Net-(D4-K)") (class "Default")
      (node (ref "D4") (pin "2") (pinfunction "K_2") (pintype "passive"))
      (node (ref "IC2") (pin "12") (pinfunction "OUT_12") (pintype "power_in"))
      (node (ref "L3") (pin "1") (pinfunction "1_1") (pintype "passive"))
    )
    (net (code "35") (name "Net-(IC1-PB6_(XTAL1{slash}TOSC1))") (class "Default")
      (node (ref "C7") (pin "2") (pinfunction "2_2") (pintype "passive"))
      (node (ref "IC1") (pin "7") (pinfunction "PB6_(XTAL1/TOSC1)_7") (pintype "bidirectional"))
      (node (ref "X2") (pin "2") (pinfunction "2_2") (pintype "passive"))
    )
    (net (code "36") (name "Net-(IC1-PB7_(XTAL2{slash}TOSC2))") (class "Default")
      (node (ref "C8") (pin "2") (pinfunction "2_2") (pintype "passive"))
      (node (ref "IC1") (pin "8") (pinfunction "PB7_(XTAL2/TOSC2)_8") (pintype "bidirectional"))
      (node (ref "X2") (pin "1") (pinfunction "1_1") (pintype "passive"))
    )
    (net (code "37") (name "Net-(IC2-FB)") (class "Default")
      (node (ref "IC2") (pin "3") (pinfunction "FB_3") (pintype "input"))
      (node (ref "R12") (pin "1") (pinfunction "1_1") (pintype "passive"))
      (node (ref "R13") (pin "2") (pinfunction "2_2") (pintype "passive"))
    )
    (net (code "38") (name "Net-(R14-Pad2)") (class "Default")
      (node (ref "R14") (pin "2") (pinfunction "2_2") (pintype "passive"))
      (node (ref "R15") (pin "1") (pinfunction "1_1") (pintype "passive"))
    )
    (net (code "39") (name "Net-(R16-Pad2)") (class "Default")
      (node (ref "R16") (pin "2") (pinfunction "2_2") (pintype "passive"))
      (node (ref "R17") (pin "1") (pinfunction "1_1") (pintype "passive"))
    )
    (net (code "40") (name "Net-(R18-Pad2)") (class "Default")
      (node (ref "R18") (pin "2") (pinfunction "2_2") (pintype "passive"))
      (node (ref "R19") (pin "1") (pinfunction "1_1") (pintype "passive"))
    )
    (net (code "41") (name "unconnected-(CN1A-RX1+-Pad23)") (class "Default")
      (node (ref "CN1") (pin "23") (pinfunction "RX1+_23") (pintype "output"))
    )
    (net (code "42") (name "unconnected-(CN1A-RX1--Pad24)") (class "Default")
      (node (ref "CN1") (pin "24") (pinfunction "RX1-_24") (pintype "output"))
    )
    (net (code "43") (name "unconnected-(CN1A-RX2+-Pad32)") (class "Default")
      (node (ref "CN1") (pin "32") (pinfunction "RX2+_32") (pintype "output"))
    )
    (net (code "44") (name "unconnected-(CN1A-RX2--Pad33)") (class "Default")
      (node (ref "CN1") (pin "33") (pinfunction "RX2-_33") (pintype "output"))
    )
    (net (code "45") (name "unconnected-(CN1A-RX3+-Pad38)") (class "Default")
      (node (ref "CN1") (pin "38") (pinfunction "RX3+_38") (pintype "output"))
    )
    (net (code "46") (name "unconnected-(CN1A-RX3--Pad39)") (class "Default")
      (node (ref "CN1") (pin "39") (pinfunction "RX3-_39") (pintype "output"))
    )
    (net (code "47") (name "unconnected-(CN1A-RX4+-Pad47)") (class "Default")
      (node (ref "CN1") (pin "47") (pinfunction "RX4+_47") (pintype "output"))
    )
    (net (code "48") (name "unconnected-(CN1A-RX4--Pad48)") (class "Default")
      (node (ref "CN1") (pin "48") (pinfunction "RX4-_48") (pintype "output"))
    )
    (net (code "49") (name "unconnected-(CN1A-RX5+-Pad53)") (class "Default")
      (node (ref "CN1") (pin "53") (pinfunction "RX5+_53") (pintype "output"))
    )
    (net (code "50") (name "unconnected-(CN1A-RX5--Pad54)") (class "Default")
      (node (ref "CN1") (pin "54") (pinfunction "RX5-_54") (pintype "output"))
    )
    (net (code "51") (name "unconnected-(CN1A-RX6+-Pad62)") (class "Default")
      (node (ref "CN1") (pin "62") (pinfunction "RX6+_62") (pintype "output"))
    )
    (net (code "52") (name "unconnected-(CN1A-RX6--Pad63)") (class "Default")
      (node (ref "CN1") (pin "63") (pinfunction "RX6-_63") (pintype "output"))
    )
    (net (code "53") (name "unconnected-(CN1A-RX7+-Pad68)") (class "Default")
      (node (ref "CN1") (pin "68") (pinfunction "RX7+_68") (pintype "output"))
    )
    (net (code "54") (name "unconnected-(CN1A-RX7--Pad69)") (class "Default")
      (node (ref "CN1") (pin "69") (pinfunction "RX7-_69") (pintype "output"))
    )
    (net (code "55") (name "unconnected-(CN1A-RX8+-Pad88)") (class "Default")
      (node (ref "CN1") (pin "88") (pinfunction "RX8+_88") (pintype "output"))
    )
    (net (code "56") (name "unconnected-(CN1A-RX8--Pad87)") (class "Default")
      (node (ref "CN1") (pin "87") (pinfunction "RX8-_87") (pintype "output"))
    )
    (net (code "57") (name "unconnected-(CN1A-RX9+-Pad94)") (class "Default")
      (node (ref "CN1") (pin "94") (pinfunction "RX9+_94") (pintype "output"))
    )
    (net (code "58") (name "unconnected-(CN1A-RX9--Pad93)") (class "Default")
      (node (ref "CN1") (pin "93") (pinfunction "RX9-_93") (pintype "output"))
    )
    (net (code "59") (name "unconnected-(CN1A-RX10+-Pad100)") (class "Default")
      (node (ref "CN1") (pin "100") (pinfunction "RX10+_100") (pintype "output"))
    )
    (net (code "60") (name "unconnected-(CN1A-RX10--Pad99)") (class "Default")
      (node (ref "CN1") (pin "99") (pinfunction "RX10-_99") (pintype "output"))
    )
    (net (code "61") (name "unconnected-(CN1A-RX11+-Pad106)") (class "Default")
      (node (ref "CN1") (pin "106") (pinfunction "RX11+_106") (pintype "output"))
    )
    (net (code "62") (name "unconnected-(CN1A-RX11--Pad105)") (class "Default")
      (node (ref "CN1") (pin "105") (pinfunction "RX11-_105") (pintype "output"))
    )
    (net (code "63") (name "unconnected-(CN1A-RX12+-Pad112)") (class "Default")
      (node (ref "CN1") (pin "112") (pinfunction "RX12+_112") (pintype "output"))
    )
    (net (code "64") (name "unconnected-(CN1A-RX12--Pad111)") (class "Default")
      (node (ref "CN1") (pin "111") (pinfunction "RX12-_111") (pintype "output"))
    )
    (net (code "65") (name "unconnected-(CN1A-RX13+-Pad118)") (class "Default")
      (node (ref "CN1") (pin "118") (pinfunction "RX13+_118") (pintype "output"))
    )
    (net (code "66") (name "unconnected-(CN1A-RX13--Pad119)") (class "Default")
      (node (ref "CN1") (pin "119") (pinfunction "RX13-_119") (pintype "output"))
    )
    (net (code "67") (name "unconnected-(CN1A-RX14+-Pad124)") (class "Default")
      (node (ref "CN1") (pin "124") (pinfunction "RX14+_124") (pintype "output"))
    )
    (net (code "68") (name "unconnected-(CN1A-RX14--Pad123)") (class "Default")
      (node (ref "CN1") (pin "123") (pinfunction "RX14-_123") (pintype "output"))
    )
    (net (code "69") (name "unconnected-(CN1A-RX15+-Pad130)") (class "Default")
      (node (ref "CN1") (pin "130") (pinfunction "RX15+_130") (pintype "output"))
    )
    (net (code "70") (name "unconnected-(CN1A-RX15--Pad129)") (class "Default")
      (node (ref "CN1") (pin "129") (pinfunction "RX15-_129") (pintype "output"))
    )
    (net (code "71") (name "unconnected-(CN1A-RX16+-Pad136)") (class "Default")
      (node (ref "CN1") (pin "136") (pinfunction "RX16+_136") (pintype "output"))
    )
    (net (code "72") (name "unconnected-(CN1A-RX16--Pad135)") (class "Default")
      (node (ref "CN1") (pin "135") (pinfunction "RX16-_135") (pintype "output"))
    )
    (net (code "73") (name "unconnected-(CN1A-RX17+-Pad142)") (class "Default")
      (node (ref "CN1") (pin "142") (pinfunction "RX17+_142") (pintype "output"))
    )
    (net (code "74") (name "unconnected-(CN1A-RX17--Pad141)") (class "Default")
      (node (ref "CN1") (pin "141") (pinfunction "RX17-_141") (pintype "output"))
    )
    (net (code "75") (name "unconnected-(CN1A-RX18+-Pad148)") (class "Default")
      (node (ref "CN1") (pin "148") (pinfunction "RX18+_148") (pintype "output"))
    )
    (net (code "76") (name "unconnected-(CN1A-RX18--Pad147)") (class "Default")
      (node (ref "CN1") (pin "147") (pinfunction "RX18-_147") (pintype "output"))
    )
    (net (code "77") (name "unconnected-(CN1A-RX19+-Pad154)") (class "Default")
      (node (ref "CN1") (pin "154") (pinfunction "RX19+_154") (pintype "output"))
    )
    (net (code "78") (name "unconnected-(CN1A-RX19--Pad153)") (class "Default")
      (node (ref "CN1") (pin "153") (pinfunction "RX19-_153") (pintype "output"))
    )
    (net (code "79") (name "unconnected-(CN1A-RX20+-Pad160)") (class "Default")
      (node (ref "CN1") (pin "160") (pinfunction "RX20+_160") (pintype "output"))
    )
    (net (code "80") (name "unconnected-(CN1A-RX20--Pad159)") (class "Default")
      (node (ref "CN1") (pin "159") (pinfunction "RX20-_159") (pintype "output"))
    )
    (net (code "81") (name "unconnected-(CN1A-TX1+-Pad20)") (class "Default")
      (node (ref "CN1") (pin "20") (pinfunction "TX1+_20") (pintype "input"))
    )
    (net (code "82") (name "unconnected-(CN1A-TX1--Pad21)") (class "Default")
      (node (ref "CN1") (pin "21") (pinfunction "TX1-_21") (pintype "input"))
    )
    (net (code "83") (name "unconnected-(CN1A-TX2+-Pad29)") (class "Default")
      (node (ref "CN1") (pin "29") (pinfunction "TX2+_29") (pintype "input"))
    )
    (net (code "84") (name "unconnected-(CN1A-TX2--Pad30)") (class "Default")
      (node (ref "CN1") (pin "30") (pinfunction "TX2-_30") (pintype "input"))
    )
    (net (code "85") (name "unconnected-(CN1A-TX3+-Pad35)") (class "Default")
      (node (ref "CN1") (pin "35") (pinfunction "TX3+_35") (pintype "input"))
    )
    (net (code "86") (name "unconnected-(CN1A-TX3--Pad36)") (class "Default")
      (node (ref "CN1") (pin "36") (pinfunction "TX3-_36") (pintype "input"))
    )
    (net (code "87") (name "unconnected-(CN1A-TX4+-Pad44)") (class "Default")
      (node (ref "CN1") (pin "44") (pinfunction "TX4+_44") (pintype "input"))
    )
    (net (code "88") (name "unconnected-(CN1A-TX4--Pad45)") (class "Default")
      (node (ref "CN1") (pin "45") (pinfunction "TX4-_45") (pintype "input"))
    )
    (net (code "89") (name "unconnected-(CN1A-TX5+-Pad50)") (class "Default")
      (node (ref "CN1") (pin "50") (pinfunction "TX5+_50") (pintype "input"))
    )
    (net (code "90") (name "unconnected-(CN1A-TX5--Pad51)") (class "Default")
      (node (ref "CN1") (pin "51") (pinfunction "TX5-_51") (pintype "input"))
    )
    (net (code "91") (name "unconnected-(CN1A-TX6+-Pad59)") (class "Default")
      (node (ref "CN1") (pin "59") (pinfunction "TX6+_59") (pintype "input"))
    )
    (net (code "92") (name "unconnected-(CN1A-TX6--Pad60)") (class "Default")
      (node (ref "CN1") (pin "60") (pinfunction "TX6-_60") (pintype "input"))
    )
    (net (code "93") (name "unconnected-(CN1A-TX7+-Pad65)") (class "Default")
      (node (ref "CN1") (pin "65") (pinfunction "TX7+_65") (pintype "input"))
    )
    (net (code "94") (name "unconnected-(CN1A-TX7--Pad66)") (class "Default")
      (node (ref "CN1") (pin "66") (pinfunction "TX7-_66") (pintype "input"))
    )
    (net (code "95") (name "unconnected-(CN1A-TX8+-Pad91)") (class "Default")
      (node (ref "CN1") (pin "91") (pinfunction "TX8+_91") (pintype "input"))
    )
    (net (code "96") (name "unconnected-(CN1A-TX8--Pad90)") (class "Default")
      (node (ref "CN1") (pin "90") (pinfunction "TX8-_90") (pintype "input"))
    )
    (net (code "97") (name "unconnected-(CN1A-TX9+-Pad97)") (class "Default")
      (node (ref "CN1") (pin "97") (pinfunction "TX9+_97") (pintype "input"))
    )
    (net (code "98") (name "unconnected-(CN1A-TX9--Pad96)") (class "Default")
      (node (ref "CN1") (pin "96") (pinfunction "TX9-_96") (pintype "input"))
    )
    (net (code "99") (name "unconnected-(CN1A-TX10+-Pad103)") (class "Default")
      (node (ref "CN1") (pin "103") (pinfunction "TX10+_103") (pintype "input"))
    )
    (net (code "100") (name "unconnected-(CN1A-TX10--Pad102)") (class "Default")
      (node (ref "CN1") (pin "102") (pinfunction "TX10-_102") (pintype "input"))
    )
    (net (code "101") (name "unconnected-(CN1A-TX11+-Pad109)") (class "Default")
      (node (ref "CN1") (pin "109") (pinfunction "TX11+_109") (pintype "input"))
    )
    (net (code "102") (name "unconnected-(CN1A-TX11--Pad108)") (class "Default")
      (node (ref "CN1") (pin "108") (pinfunction "TX11-_108") (pintype "input"))
    )
    (net (code "103") (name "unconnected-(CN1A-TX12+-Pad115)") (class "Default")
      (node (ref "CN1") (pin "115") (pinfunction "TX12+_115") (pintype "input"))
    )
    (net (code "104") (name "unconnected-(CN1A-TX12--Pad114)") (class "Default")
      (node (ref "CN1") (pin "114") (pinfunction "TX12-_114") (pintype "input"))
    )
    (net (code "105") (name "unconnected-(CN1A-TX13+-Pad121)") (class "Default")
      (node (ref "CN1") (pin "121") (pinfunction "TX13+_121") (pintype "input"))
    )
    (net (code "106") (name "unconnected-(CN1A-TX13--Pad120)") (class "Default")
      (node (ref "CN1") (pin "120") (pinfunction "TX13-_120") (pintype "input"))
    )
    (net (code "107") (name "unconnected-(CN1A-TX14+-Pad127)") (class "Default")
      (node (ref "CN1") (pin "127") (pinfunction "TX14+_127") (pintype "input"))
    )
    (net (code "108") (name "unconnected-(CN1A-TX14--Pad126)") (class "Default")
      (node (ref "CN1") (pin "126") (pinfunction "TX14-_126") (pintype "input"))
    )
    (net (code "109") (name "unconnected-(CN1A-TX15+-Pad133)") (class "Default")
      (node (ref "CN1") (pin "133") (pinfunction "TX15+_133") (pintype "input"))
    )
    (net (code "110") (name "unconnected-(CN1A-TX15--Pad132)") (class "Default")
      (node (ref "CN1") (pin "132") (pinfunction "TX15-_132") (pintype "input"))
    )
    (net (code "111") (name "unconnected-(CN1A-TX16+-Pad139)") (class "Default")
      (node (ref "CN1") (pin "139") (pinfunction "TX16+_139") (pintype "input"))
    )
    (net (code "112") (name "unconnected-(CN1A-TX16--Pad138)") (class "Default")
      (node (ref "CN1") (pin "138") (pinfunction "TX16-_138") (pintype "input"))
    )
    (net (code "113") (name "unconnected-(CN1A-TX17+-Pad145)") (class "Default")
      (node (ref "CN1") (pin "145") (pinfunction "TX17+_145") (pintype "input"))
    )
    (net (code "114") (name "unconnected-(CN1A-TX17--Pad144)") (class "Default")
      (node (ref "CN1") (pin "144") (pinfunction "TX17-_144") (pintype "input"))
    )
    (net (code "115") (name "unconnected-(CN1A-TX18+-Pad151)") (class "Default")
      (node (ref "CN1") (pin "151") (pinfunction "TX18+_151") (pintype "input"))
    )
    (net (code "116") (name "unconnected-(CN1A-TX18--Pad150)") (class "Default")
      (node (ref "CN1") (pin "150") (pinfunction "TX18-_150") (pintype "input"))
    )
    (net (code "117") (name "unconnected-(CN1A-TX19+-Pad157)") (class "Default")
      (node (ref "CN1") (pin "157") (pinfunction "TX19+_157") (pintype "input"))
    )
    (net (code "118") (name "unconnected-(CN1A-TX19--Pad156)") (class "Default")
      (node (ref "CN1") (pin "156") (pinfunction "TX19-_156") (pintype "input"))
    )
    (net (code "119") (name "unconnected-(CN1A-TX20+-Pad163)") (class "Default")
      (node (ref "CN1") (pin "163") (pinfunction "TX20+_163") (pintype "input"))
    )
    (net (code "120") (name "unconnected-(CN1A-TX20--Pad162)") (class "Default")
      (node (ref "CN1") (pin "162") (pinfunction "TX20-_162") (pintype "input"))
    )
    (net (code "121") (name "unconnected-(CN1B-CLK1+-Pad74)") (class "Default")
      (node (ref "CN1") (pin "74") (pinfunction "CLK1+_74") (pintype "output"))
    )
    (net (code "122") (name "unconnected-(CN1B-CLK1--Pad75)") (class "Default")
      (node (ref "CN1") (pin "75") (pinfunction "CLK1-_75") (pintype "output"))
    )
    (net (code "123") (name "unconnected-(CN1B-CLK2+-Pad77)") (class "Default")
      (node (ref "CN1") (pin "77") (pinfunction "CLK2+_77") (pintype "input"))
    )
    (net (code "124") (name "unconnected-(CN1B-CLK2--Pad78)") (class "Default")
      (node (ref "CN1") (pin "78") (pinfunction "CLK2-_78") (pintype "input"))
    )
    (net (code "125") (name "unconnected-(CN1B-CLK3+-Pad80)") (class "Default")
      (node (ref "CN1") (pin "80") (pinfunction "CLK3+_80") (pintype "output"))
    )
    (net (code "126") (name "unconnected-(CN1B-CLK3--Pad81)") (class "Default")
      (node (ref "CN1") (pin "81") (pinfunction "CLK3-_81") (pintype "output"))
    )
    (net (code "127") (name "unconnected-(CN1B-RSRVD-Pad6)") (class "Default")
      (node (ref "CN1") (pin "6") (pinfunction "RSRVD_6") (pintype "passive"))
    )
    (net (code "128") (name "unconnected-(CN1B-RSRVD-Pad8)") (class "Default")
      (node (ref "CN1") (pin "8") (pinfunction "RSRVD_8") (pintype "passive"))
    )
    (net (code "129") (name "unconnected-(CN1B-TCLK-Pad165)") (class "Default")
      (node (ref "CN1") (pin "165") (pinfunction "TCLK_165") (pintype "bidirectional"))
    )
    (net (code "130") (name "unconnected-(CN1B-TDI-Pad169)") (class "Default")
      (node (ref "CN1") (pin "169") (pinfunction "TDI_169") (pintype "bidirectional"))
    )
    (net (code "131") (name "unconnected-(CN1B-TDO-Pad168)") (class "Default")
      (node (ref "CN1") (pin "168") (pinfunction "TDO_168") (pintype "bidirectional"))
    )
    (net (code "132") (name "unconnected-(CN1B-TMS-Pad166)") (class "Default")
      (node (ref "CN1") (pin "166") (pinfunction "TMS_166") (pintype "bidirectional"))
    )
    (net (code "133") (name "unconnected-(CN1B-TRST-Pad167)") (class "Default")
      (node (ref "CN1") (pin "167") (pinfunction "TRST_167") (pintype "bidirectional"))
    )
    (net (code "134") (name "unconnected-(IC1-ADC6-Pad19)") (class "Default")
      (node (ref "IC1") (pin "19") (pinfunction "ADC6_19") (pintype "input"))
    )
    (net (code "135") (name "unconnected-(IC1-ADC7-Pad22)") (class "Default")
      (node (ref "IC1") (pin "22") (pinfunction "ADC7_22") (pintype "input"))
    )
    (net (code "136") (name "unconnected-(IC1-PB3_(MOSI{slash}OC2)-Pad15)") (class "Default")
      (node (ref "IC1") (pin "15") (pinfunction "PB3_(MOSI/OC2)_15") (pintype "bidirectional"))
    )
    (net (code "137") (name "unconnected-(IC1-PB4_(MISO)-Pad16)") (class "Default")
      (node (ref "IC1") (pin "16") (pinfunction "PB4_(MISO)_16") (pintype "bidirectional"))
    )
    (net (code "138") (name "unconnected-(IC1-PB5_(SCK)-Pad17)") (class "Default")
      (node (ref "IC1") (pin "17") (pinfunction "PB5_(SCK)_17") (pintype "bidirectional"))
    )
    (net (code "139") (name "unconnected-(IC1-PC3_(ADC3)-Pad26)") (class "Default")
      (node (ref "IC1") (pin "26") (pinfunction "PC3_(ADC3)_26") (pintype "bidirectional"))
    )
    (net (code "140") (name "unconnected-(IC1-PD0_(RXD)-Pad30)") (class "Default")
      (node (ref "IC1") (pin "30") (pinfunction "PD0_(RXD)_30") (pintype "bidirectional"))
    )
    (net (code "141") (name "unconnected-(IC1-PD1_(TXD)-Pad31)") (class "Default")
      (node (ref "IC1") (pin "31") (pinfunction "PD1_(TXD)_31") (pintype "bidirectional"))
    )
    (net (code "142") (name "unconnected-(IC2-NC-Pad1)") (class "Default")
      (node (ref "IC2") (pin "1") (pinfunction "NC_1") (pintype "passive"))
    )
    (net (code "143") (name "unconnected-(IC2-NC-Pad2)") (class "Default")
      (node (ref "IC2") (pin "2") (pinfunction "NC_2") (pintype "passive"))
    )
    (net (code "144") (name "unconnected-(IC2-NC-Pad7)") (class "Default")
      (node (ref "IC2") (pin "7") (pinfunction "NC_7") (pintype "passive"))
    )
    (net (code "145") (name "unconnected-(IC2-NC-Pad8)") (class "Default")
      (node (ref "IC2") (pin "8") (pinfunction "NC_8") (pintype "passive"))
    )
    (net (code "146") (name "unconnected-(IC2-NC-Pad9)") (class "Default")
      (node (ref "IC2") (pin "9") (pinfunction "NC_9") (pintype "passive"))
    )
    (net (code "147") (name "unconnected-(IC2-NC-Pad11)") (class "Default")
      (node (ref "IC2") (pin "11") (pinfunction "NC_11") (pintype "passive"))
    )
    (net (code "148") (name "unconnected-(IC2-NC-Pad13)") (class "Default")
      (node (ref "IC2") (pin "13") (pinfunction "NC_13") (pintype "passive"))
    )
    (net (code "149") (name "unconnected-(IC2-NC-Pad14)") (class "Default")
      (node (ref "IC2") (pin "14") (pinfunction "NC_14") (pintype "passive"))
    )
  )
)
